# STM32.net
KiCad netlist of a schematic drawn in Altium Designer
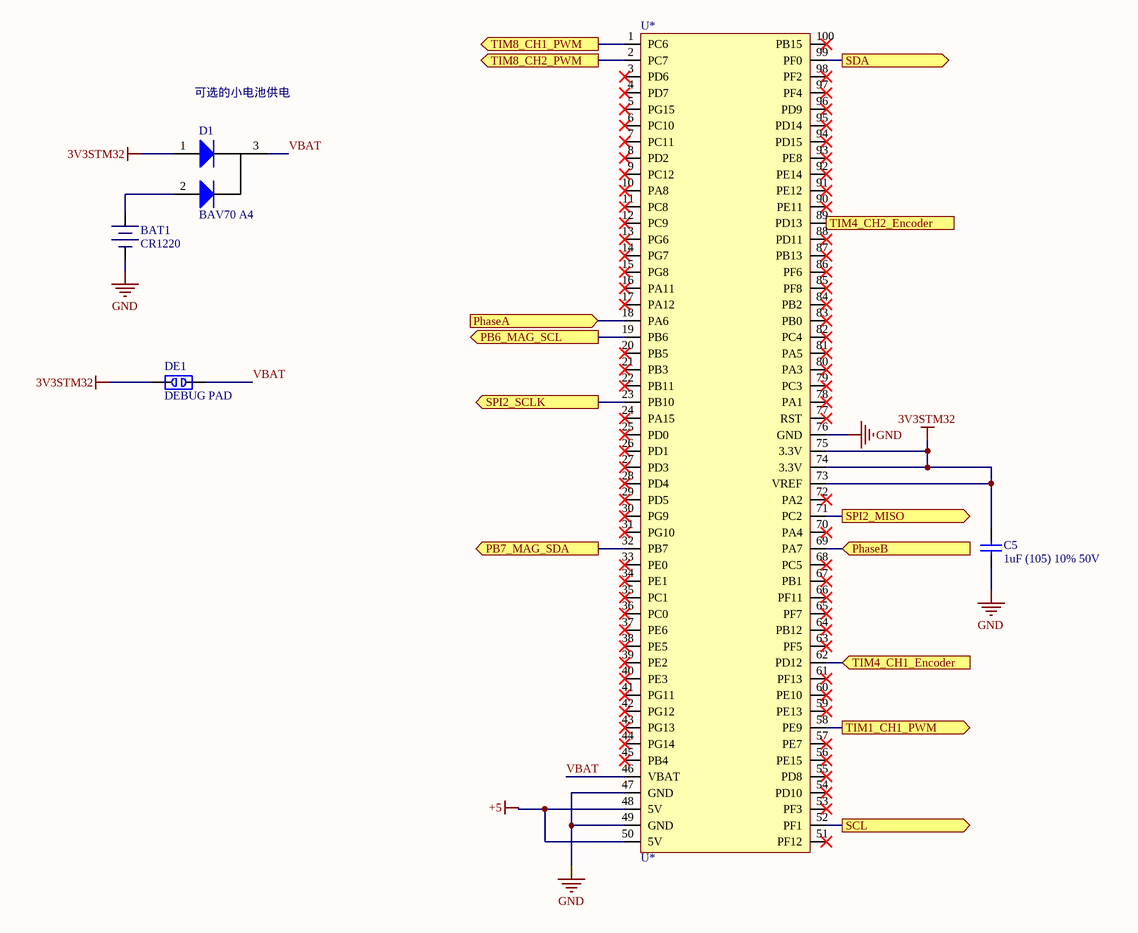
[diagram p0: STM32.SchDoc]

(export (version "E")
  (design (tool "Eeschema 10.0.6"))
  (components
    (comp (ref "BAT1") (value "CR1220") (footprint "CR1220-A") (libsource (lib "纽扣电池座") (part "CR1220")))
    (comp (ref "C5")
      (value "1uF (105) 10% 50V")
      (footprint "0603_C")
      (description "贴片电容")
      (libsource (lib "Miscellaneous Devices LC") (part "0603 1uF (105) 10% 50V"))
    )
    (comp (ref "D1")
      (value "BAV70 A4")
      (footprint "SOT-23(SOT-23-3)")
      (description "开关二极管")
      (libsource (lib "Miscellaneous Devices LC") (part "SOT-23 BAV70 A4"))
    )
    (comp (ref "DE1")
      (value "DEBUG PAD")
      (footprint "DEBUG_B")
      (description "调试断点焊盘")
      (fields (field (name "版权归属") "源创客"))
      (libsource (lib "15.1 - 未分类器件") (part "DEBUG"))
    )
    (comp (ref "U*")
      (value "U*")
      (footprint "STM32F407MiniBoard")
      (libsource (lib "Schlib1") (part "STM32F407MiniBoard"))
    )
  )
  (nets
    (net (code "1") (name "+5") (class "Default")
      (node (ref "U*") (pin "48") (pinfunction "5V_48") (pintype "passive"))
      (node (ref "U*") (pin "50") (pinfunction "5V_50") (pintype "passive"))
    )
    (net (code "2") (name "/PB6_MAG_SCL") (class "Default")
      (node (ref "U*") (pin "19") (pinfunction "PB6_19") (pintype "passive"))
    )
    (net (code "3") (name "/PB7_MAG_SDA") (class "Default")
      (node (ref "U*") (pin "32") (pinfunction "PB7_32") (pintype "passive"))
    )
    (net (code "4") (name "/PhaseA") (class "Default")
      (node (ref "U*") (pin "18") (pinfunction "PA6_18") (pintype "passive"))
    )
    (net (code "5") (name "/PhaseB") (class "Default")
      (node (ref "U*") (pin "69") (pinfunction "PA7_69") (pintype "passive"))
    )
    (net (code "6") (name "/SCL") (class "Default")
      (node (ref "U*") (pin "52") (pinfunction "PF1_52") (pintype "passive"))
    )
    (net (code "7") (name "/SDA") (class "Default")
      (node (ref "U*") (pin "99") (pinfunction "PF0_99") (pintype "passive"))
    )
    (net (code "8") (name "/SPI2_MISO") (class "Default")
      (node (ref "U*") (pin "71") (pinfunction "PC2_71") (pintype "passive"))
    )
    (net (code "9") (name "/SPI2_SCLK") (class "Default")
      (node (ref "U*") (pin "23") (pinfunction "PB10_23") (pintype "passive"))
    )
    (net (code "10") (name "/TIM1_CH1_PWM") (class "Default")
      (node (ref "U*") (pin "58") (pinfunction "PE9_58") (pintype "passive"))
    )
    (net (code "11") (name "/TIM4_CH1_Encoder") (class "Default")
      (node (ref "U*") (pin "62") (pinfunction "PD12_62") (pintype "passive"))
    )
    (net (code "12") (name "/TIM4_CH2_Encoder") (class "Default")
      (node (ref "U*") (pin "89") (pinfunction "PD13_89") (pintype "passive"))
    )
    (net (code "13") (name "/TIM8_CH1_PWM") (class "Default")
      (node (ref "U*") (pin "1") (pinfunction "PC6_1") (pintype "passive"))
    )
    (net (code "14") (name "/TIM8_CH2_PWM") (class "Default")
      (node (ref "U*") (pin "2") (pinfunction "PC7_2") (pintype "passive"))
    )
    (net (code "15") (name "/VBAT") (class "Default")
      (node (ref "D1") (pin "3") (pinfunction "K_3") (pintype "passive"))
      (node (ref "DE1") (pin "2") (pinfunction "2_2") (pintype "passive"))
      (node (ref "U*") (pin "46") (pinfunction "VBAT_46") (pintype "passive"))
    )
    (net (code "16") (name "3V3STM32") (class "Default")
      (node (ref "C5") (pin "2") (pinfunction "2_2") (pintype "passive"))
      (node (ref "D1") (pin "1") (pinfunction "A_1") (pintype "passive"))
      (node (ref "DE1") (pin "1") (pinfunction "1_1") (pintype "passive"))
      (node (ref "U*") (pin "73") (pinfunction "VREF_73") (pintype "passive"))
      (node (ref "U*") (pin "74") (pinfunction "3.3V_74") (pintype "passive"))
      (node (ref "U*") (pin "75") (pinfunction "3.3V_75") (pintype "passive"))
    )
    (net (code "17") (name "GND") (class "Default")
      (node (ref "BAT1") (pin "2") (pinfunction "2_2") (pintype "passive"))
      (node (ref "C5") (pin "1") (pinfunction "1_1") (pintype "passive"))
      (node (ref "U*") (pin "47") (pinfunction "GND_47") (pintype "passive"))
      (node (ref "U*") (pin "49") (pinfunction "GND_49") (pintype "passive"))
      (node (ref "U*") (pin "76") (pinfunction "GND_76") (pintype "passive"))
    )
    (net (code "18") (name "Net-(BAT1-Pad1)") (class "Default")
      (node (ref "BAT1") (pin "1") (pinfunction "1_1") (pintype "passive"))
      (node (ref "D1") (pin "2") (pinfunction "A_2") (pintype "passive"))
    )
    (net (code "19") (name "unconnected-(U*-PA1-Pad78)") (class "Default")
      (node (ref "U*") (pin "78") (pinfunction "PA1_78") (pintype "passive+no_connect"))
    )
    (net (code "20") (name "unconnected-(U*-PA2-Pad72)") (class "Default")
      (node (ref "U*") (pin "72") (pinfunction "PA2_72") (pintype "passive+no_connect"))
    )
    (net (code "21") (name "unconnected-(U*-PA3-Pad80)") (class "Default")
      (node (ref "U*") (pin "80") (pinfunction "PA3_80") (pintype "passive+no_connect"))
    )
    (net (code "22") (name "unconnected-(U*-PA4-Pad70)") (class "Default")
      (node (ref "U*") (pin "70") (pinfunction "PA4_70") (pintype "passive+no_connect"))
    )
    (net (code "23") (name "unconnected-(U*-PA5-Pad81)") (class "Default")
      (node (ref "U*") (pin "81") (pinfunction "PA5_81") (pintype "passive+no_connect"))
    )
    (net (code "24") (name "unconnected-(U*-PA8-Pad10)") (class "Default")
      (node (ref "U*") (pin "10") (pinfunction "PA8_10") (pintype "passive+no_connect"))
    )
    (net (code "25") (name "unconnected-(U*-PA11-Pad16)") (class "Default")
      (node (ref "U*") (pin "16") (pinfunction "PA11_16") (pintype "passive+no_connect"))
    )
    (net (code "26") (name "unconnected-(U*-PA12-Pad17)") (class "Default")
      (node (ref "U*") (pin "17") (pinfunction "PA12_17") (pintype "passive+no_connect"))
    )
    (net (code "27") (name "unconnected-(U*-PA15-Pad24)") (class "Default")
      (node (ref "U*") (pin "24") (pinfunction "PA15_24") (pintype "passive+no_connect"))
    )
    (net (code "28") (name "unconnected-(U*-PB0-Pad83)") (class "Default")
      (node (ref "U*") (pin "83") (pinfunction "PB0_83") (pintype "passive+no_connect"))
    )
    (net (code "29") (name "unconnected-(U*-PB1-Pad67)") (class "Default")
      (node (ref "U*") (pin "67") (pinfunction "PB1_67") (pintype "passive+no_connect"))
    )
    (net (code "30") (name "unconnected-(U*-PB2-Pad84)") (class "Default")
      (node (ref "U*") (pin "84") (pinfunction "PB2_84") (pintype "passive+no_connect"))
    )
    (net (code "31") (name "unconnected-(U*-PB3-Pad21)") (class "Default")
      (node (ref "U*") (pin "21") (pinfunction "PB3_21") (pintype "passive+no_connect"))
    )
    (net (code "32") (name "unconnected-(U*-PB4-Pad45)") (class "Default")
      (node (ref "U*") (pin "45") (pinfunction "PB4_45") (pintype "passive+no_connect"))
    )
    (net (code "33") (name "unconnected-(U*-PB5-Pad20)") (class "Default")
      (node (ref "U*") (pin "20") (pinfunction "PB5_20") (pintype "passive+no_connect"))
    )
    (net (code "34") (name "unconnected-(U*-PB11-Pad22)") (class "Default")
      (node (ref "U*") (pin "22") (pinfunction "PB11_22") (pintype "passive+no_connect"))
    )
    (net (code "35") (name "unconnected-(U*-PB12-Pad64)") (class "Default")
      (node (ref "U*") (pin "64") (pinfunction "PB12_64") (pintype "passive+no_connect"))
    )
    (net (code "36") (name "unconnected-(U*-PB13-Pad87)") (class "Default")
      (node (ref "U*") (pin "87") (pinfunction "PB13_87") (pintype "passive+no_connect"))
    )
    (net (code "37") (name "unconnected-(U*-PB15-Pad100)") (class "Default")
      (node (ref "U*") (pin "100") (pinfunction "PB15_100") (pintype "passive+no_connect"))
    )
    (net (code "38") (name "unconnected-(U*-PC0-Pad36)") (class "Default")
      (node (ref "U*") (pin "36") (pinfunction "PC0_36") (pintype "passive+no_connect"))
    )
    (net (code "39") (name "unconnected-(U*-PC1-Pad35)") (class "Default")
      (node (ref "U*") (pin "35") (pinfunction "PC1_35") (pintype "passive+no_connect"))
    )
    (net (code "40") (name "unconnected-(U*-PC3-Pad79)") (class "Default")
      (node (ref "U*") (pin "79") (pinfunction "PC3_79") (pintype "passive+no_connect"))
    )
    (net (code "41") (name "unconnected-(U*-PC4-Pad82)") (class "Default")
      (node (ref "U*") (pin "82") (pinfunction "PC4_82") (pintype "passive+no_connect"))
    )
    (net (code "42") (name "unconnected-(U*-PC5-Pad68)") (class "Default")
      (node (ref "U*") (pin "68") (pinfunction "PC5_68") (pintype "passive+no_connect"))
    )
    (net (code "43") (name "unconnected-(U*-PC8-Pad11)") (class "Default")
      (node (ref "U*") (pin "11") (pinfunction "PC8_11") (pintype "passive+no_connect"))
    )
    (net (code "44") (name "unconnected-(U*-PC9-Pad12)") (class "Default")
      (node (ref "U*") (pin "12") (pinfunction "PC9_12") (pintype "passive+no_connect"))
    )
    (net (code "45") (name "unconnected-(U*-PC10-Pad6)") (class "Default")
      (node (ref "U*") (pin "6") (pinfunction "PC10_6") (pintype "passive+no_connect"))
    )
    (net (code "46") (name "unconnected-(U*-PC11-Pad7)") (class "Default")
      (node (ref "U*") (pin "7") (pinfunction "PC11_7") (pintype "passive+no_connect"))
    )
    (net (code "47") (name "unconnected-(U*-PC12-Pad9)") (class "Default")
      (node (ref "U*") (pin "9") (pinfunction "PC12_9") (pintype "passive+no_connect"))
    )
    (net (code "48") (name "unconnected-(U*-PD0-Pad25)") (class "Default")
      (node (ref "U*") (pin "25") (pinfunction "PD0_25") (pintype "passive+no_connect"))
    )
    (net (code "49") (name "unconnected-(U*-PD1-Pad26)") (class "Default")
      (node (ref "U*") (pin "26") (pinfunction "PD1_26") (pintype "passive+no_connect"))
    )
    (net (code "50") (name "unconnected-(U*-PD2-Pad8)") (class "Default")
      (node (ref "U*") (pin "8") (pinfunction "PD2_8") (pintype "passive+no_connect"))
    )
    (net (code "51") (name "unconnected-(U*-PD3-Pad27)") (class "Default")
      (node (ref "U*") (pin "27") (pinfunction "PD3_27") (pintype "passive+no_connect"))
    )
    (net (code "52") (name "unconnected-(U*-PD4-Pad28)") (class "Default")
      (node (ref "U*") (pin "28") (pinfunction "PD4_28") (pintype "passive+no_connect"))
    )
    (net (code "53") (name "unconnected-(U*-PD5-Pad29)") (class "Default")
      (node (ref "U*") (pin "29") (pinfunction "PD5_29") (pintype "passive+no_connect"))
    )
    (net (code "54") (name "unconnected-(U*-PD6-Pad3)") (class "Default")
      (node (ref "U*") (pin "3") (pinfunction "PD6_3") (pintype "passive+no_connect"))
    )
    (net (code "55") (name "unconnected-(U*-PD7-Pad4)") (class "Default")
      (node (ref "U*") (pin "4") (pinfunction "PD7_4") (pintype "passive+no_connect"))
    )
    (net (code "56") (name "unconnected-(U*-PD8-Pad55)") (class "Default")
      (node (ref "U*") (pin "55") (pinfunction "PD8_55") (pintype "passive+no_connect"))
    )
    (net (code "57") (name "unconnected-(U*-PD9-Pad96)") (class "Default")
      (node (ref "U*") (pin "96") (pinfunction "PD9_96") (pintype "passive+no_connect"))
    )
    (net (code "58") (name "unconnected-(U*-PD10-Pad54)") (class "Default")
      (node (ref "U*") (pin "54") (pinfunction "PD10_54") (pintype "passive+no_connect"))
    )
    (net (code "59") (name "unconnected-(U*-PD11-Pad88)") (class "Default")
      (node (ref "U*") (pin "88") (pinfunction "PD11_88") (pintype "passive+no_connect"))
    )
    (net (code "60") (name "unconnected-(U*-PD14-Pad95)") (class "Default")
      (node (ref "U*") (pin "95") (pinfunction "PD14_95") (pintype "passive+no_connect"))
    )
    (net (code "61") (name "unconnected-(U*-PD15-Pad94)") (class "Default")
      (node (ref "U*") (pin "94") (pinfunction "PD15_94") (pintype "passive+no_connect"))
    )
    (net (code "62") (name "unconnected-(U*-PE0-Pad33)") (class "Default")
      (node (ref "U*") (pin "33") (pinfunction "PE0_33") (pintype "passive+no_connect"))
    )
    (net (code "63") (name "unconnected-(U*-PE1-Pad34)") (class "Default")
      (node (ref "U*") (pin "34") (pinfunction "PE1_34") (pintype "passive+no_connect"))
    )
    (net (code "64") (name "unconnected-(U*-PE2-Pad39)") (class "Default")
      (node (ref "U*") (pin "39") (pinfunction "PE2_39") (pintype "passive+no_connect"))
    )
    (net (code "65") (name "unconnected-(U*-PE3-Pad40)") (class "Default")
      (node (ref "U*") (pin "40") (pinfunction "PE3_40") (pintype "passive+no_connect"))
    )
    (net (code "66") (name "unconnected-(U*-PE5-Pad38)") (class "Default")
      (node (ref "U*") (pin "38") (pinfunction "PE5_38") (pintype "passive+no_connect"))
    )
    (net (code "67") (name "unconnected-(U*-PE6-Pad37)") (class "Default")
      (node (ref "U*") (pin "37") (pinfunction "PE6_37") (pintype "passive+no_connect"))
    )
    (net (code "68") (name "unconnected-(U*-PE7-Pad57)") (class "Default")
      (node (ref "U*") (pin "57") (pinfunction "PE7_57") (pintype "passive+no_connect"))
    )
    (net (code "69") (name "unconnected-(U*-PE8-Pad93)") (class "Default")
      (node (ref "U*") (pin "93") (pinfunction "PE8_93") (pintype "passive+no_connect"))
    )
    (net (code "70") (name "unconnected-(U*-PE10-Pad60)") (class "Default")
      (node (ref "U*") (pin "60") (pinfunction "PE10_60") (pintype "passive+no_connect"))
    )
    (net (code "71") (name "unconnected-(U*-PE11-Pad90)") (class "Default")
      (node (ref "U*") (pin "90") (pinfunction "PE11_90") (pintype "passive+no_connect"))
    )
    (net (code "72") (name "unconnected-(U*-PE12-Pad91)") (class "Default")
      (node (ref "U*") (pin "91") (pinfunction "PE12_91") (pintype "passive+no_connect"))
    )
    (net (code "73") (name "unconnected-(U*-PE13-Pad59)") (class "Default")
      (node (ref "U*") (pin "59") (pinfunction "PE13_59") (pintype "passive+no_connect"))
    )
    (net (code "74") (name "unconnected-(U*-PE14-Pad92)") (class "Default")
      (node (ref "U*") (pin "92") (pinfunction "PE14_92") (pintype "passive+no_connect"))
    )
    (net (code "75") (name "unconnected-(U*-PE15-Pad56)") (class "Default")
      (node (ref "U*") (pin "56") (pinfunction "PE15_56") (pintype "passive+no_connect"))
    )
    (net (code "76") (name "unconnected-(U*-PF2-Pad98)") (class "Default")
      (node (ref "U*") (pin "98") (pinfunction "PF2_98") (pintype "passive+no_connect"))
    )
    (net (code "77") (name "unconnected-(U*-PF3-Pad53)") (class "Default")
      (node (ref "U*") (pin "53") (pinfunction "PF3_53") (pintype "passive+no_connect"))
    )
    (net (code "78") (name "unconnected-(U*-PF4-Pad97)") (class "Default")
      (node (ref "U*") (pin "97") (pinfunction "PF4_97") (pintype "passive+no_connect"))
    )
    (net (code "79") (name "unconnected-(U*-PF5-Pad63)") (class "Default")
      (node (ref "U*") (pin "63") (pinfunction "PF5_63") (pintype "passive+no_connect"))
    )
    (net (code "80") (name "unconnected-(U*-PF6-Pad86)") (class "Default")
      (node (ref "U*") (pin "86") (pinfunction "PF6_86") (pintype "passive+no_connect"))
    )
    (net (code "81") (name "unconnected-(U*-PF7-Pad65)") (class "Default")
      (node (ref "U*") (pin "65") (pinfunction "PF7_65") (pintype "passive+no_connect"))
    )
    (net (code "82") (name "unconnected-(U*-PF8-Pad85)") (class "Default")
      (node (ref "U*") (pin "85") (pinfunction "PF8_85") (pintype "passive+no_connect"))
    )
    (net (code "83") (name "unconnected-(U*-PF11-Pad66)") (class "Default")
      (node (ref "U*") (pin "66") (pinfunction "PF11_66") (pintype "passive+no_connect"))
    )
    (net (code "84") (name "unconnected-(U*-PF12-Pad51)") (class "Default")
      (node (ref "U*") (pin "51") (pinfunction "PF12_51") (pintype "passive+no_connect"))
    )
    (net (code "85") (name "unconnected-(U*-PF13-Pad61)") (class "Default")
      (node (ref "U*") (pin "61") (pinfunction "PF13_61") (pintype "passive+no_connect"))
    )
    (net (code "86") (name "unconnected-(U*-PG6-Pad13)") (class "Default")
      (node (ref "U*") (pin "13") (pinfunction "PG6_13") (pintype "passive+no_connect"))
    )
    (net (code "87") (name "unconnected-(U*-PG7-Pad14)") (class "Default")
      (node (ref "U*") (pin "14") (pinfunction "PG7_14") (pintype "passive+no_connect"))
    )
    (net (code "88") (name "unconnected-(U*-PG8-Pad15)") (class "Default")
      (node (ref "U*") (pin "15") (pinfunction "PG8_15") (pintype "passive+no_connect"))
    )
    (net (code "89") (name "unconnected-(U*-PG9-Pad30)") (class "Default")
      (node (ref "U*") (pin "30") (pinfunction "PG9_30") (pintype "passive+no_connect"))
    )
    (net (code "90") (name "unconnected-(U*-PG10-Pad31)") (class "Default")
      (node (ref "U*") (pin "31") (pinfunction "PG10_31") (pintype "passive+no_connect"))
    )
    (net (code "91") (name "unconnected-(U*-PG11-Pad41)") (class "Default")
      (node (ref "U*") (pin "41") (pinfunction "PG11_41") (pintype "passive+no_connect"))
    )
    (net (code "92") (name "unconnected-(U*-PG12-Pad42)") (class "Default")
      (node (ref "U*") (pin "42") (pinfunction "PG12_42") (pintype "passive+no_connect"))
    )
    (net (code "93") (name "unconnected-(U*-PG13-Pad43)") (class "Default")
      (node (ref "U*") (pin "43") (pinfunction "PG13_43") (pintype "passive+no_connect"))
    )
    (net (code "94") (name "unconnected-(U*-PG14-Pad44)") (class "Default")
      (node (ref "U*") (pin "44") (pinfunction "PG14_44") (pintype "passive+no_connect"))
    )
    (net (code "95") (name "unconnected-(U*-PG15-Pad5)") (class "Default")
      (node (ref "U*") (pin "5") (pinfunction "PG15_5") (pintype "passive+no_connect"))
    )
    (net (code "96") (name "unconnected-(U*-RST-Pad77)") (class "Default")
      (node (ref "U*") (pin "77") (pinfunction "RST_77") (pintype "passive+no_connect"))
    )
  )
)
